# Speaker_Module.net
KiCad netlist of a schematic drawn in Altium Designer
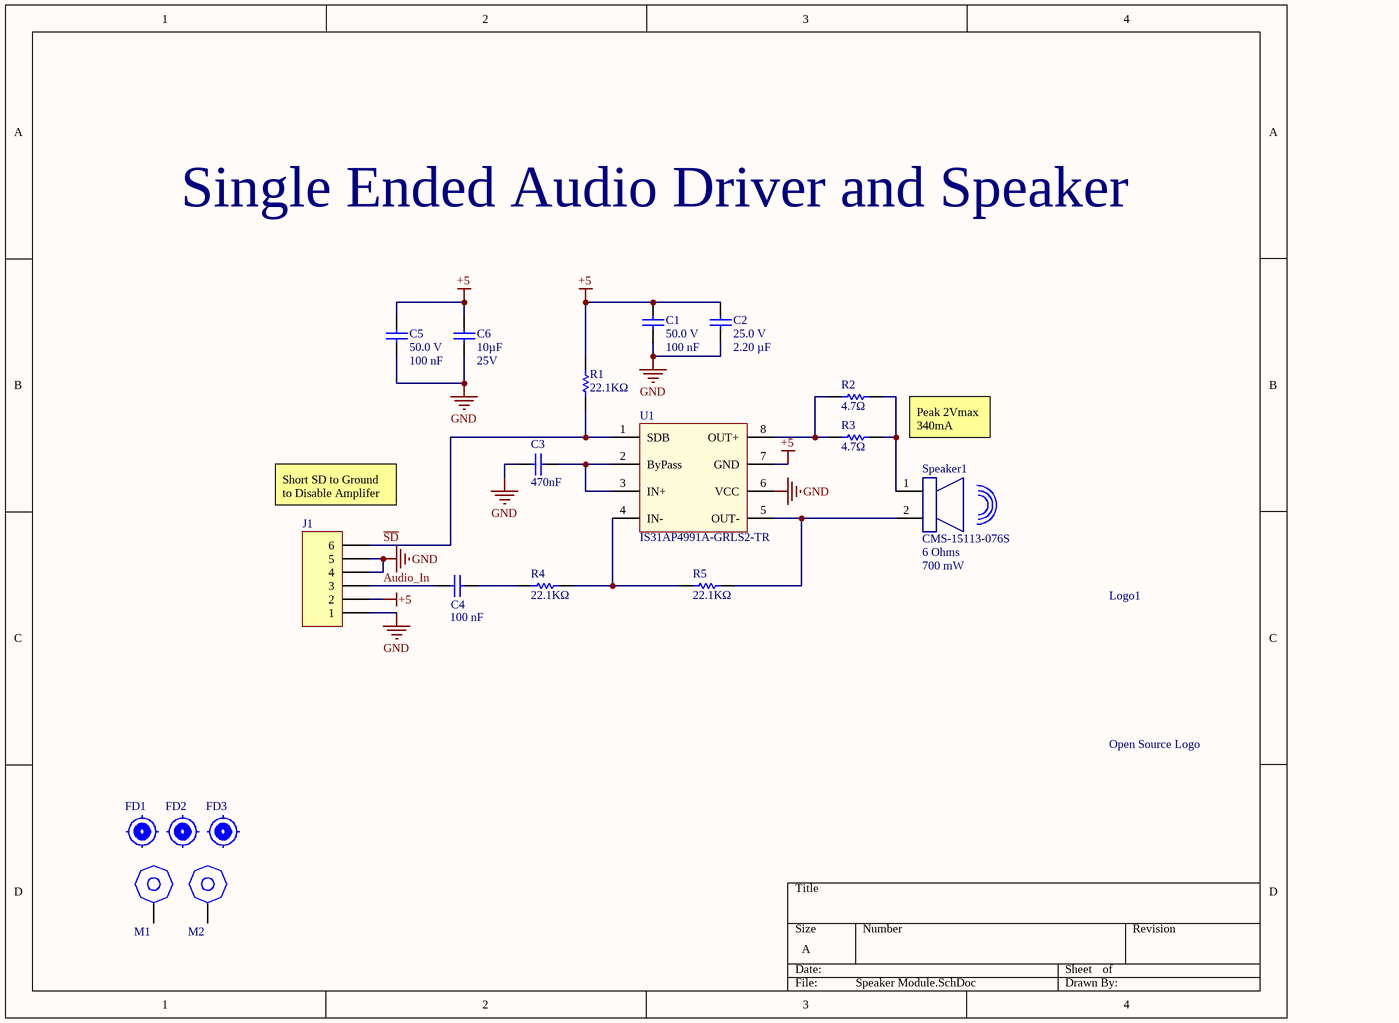
[diagram p0: Speaker Module.SchDoc]

(export (version "E")
  (design (tool "Eeschema 10.0.6"))
  (components
    (comp (ref "C1")
      (value "08055C104JAT2A")
      (footprint "Cap,0805")
      (description "Capacitor; Ceramic; Cap 0.1 uF; Tol 5%; Vol-Rtg 50 VDC; SMT; 0805; X7R; Tape & Reel")
      (fields (field (name "VOLTAGE RATING (DC)") "50.0 V") (field (name "CAPACITANCE") "100 nF"))
      (libsource (lib "Master Nov2021") (part "Cap,0805,100nf,50V,5%,08055C104JAT2A"))
    )
    (comp (ref "C2")
      (value "AVX 08053C225KAT2A")
      (footprint "CAP, 0805, HD")
      (description "0805 2.2 uF 25 V ±10 % Tolerance X7R SMT Multilayer Ceramic Capacitor")
      (fields
        (field (name "MANUFACTURER PART NUMBER") "08053C225KAT2A")
        (field (name "VOLTAGE RATING (DC)") "25.0 V")
        (field (name "CAPACITANCE") "2.20 µF")
      )
      (libsource (lib "Master Nov2021") (part "Cap,0805,2.2uF,±10%,25V,08053C225KAT2A"))
    )
    (comp (ref "C3")
      (value "CGA4J2X7R1E474K125AA")
      (footprint "Cap,0805")
      (description "0.47µF ±10% 25V Ceramic Capacitor X7R 0805 (2012 Metric)")
      (fields (field (name "MANUFACTURER") "TDK Corporation") (field (name "CAPACITANCE") "470nF"))
      (libsource (lib "Master Nov2021") (part "Cap,0805,470nf,25V,10%,CGA4J2X7R1E474K125AA"))
    )
    (comp (ref "C4")
      (value "08055C104JAT2A")
      (footprint "Cap,0805")
      (description "Capacitor; Ceramic; Cap 0.1 uF; Tol 5%; Vol-Rtg 50 VDC; SMT; 0805; X7R; Tape & Reel")
      (fields (field (name "CAPACITANCE") "100 nF"))
      (libsource (lib "Master Nov2021") (part "Cap,0805,100nf,50V,5%,08055C104JAT2A"))
    )
    (comp (ref "C5")
      (value "08055C104JAT2A")
      (footprint "Cap,0805")
      (description "Capacitor; Ceramic; Cap 0.1 uF; Tol 5%; Vol-Rtg 50 VDC; SMT; 0805; X7R; Tape & Reel")
      (fields (field (name "VOLTAGE RATING (DC)") "50.0 V") (field (name "CAPACITANCE") "100 nF"))
      (libsource (lib "Master Nov2021") (part "Cap,0805,100nf,50V,5%,08055C104JAT2A"))
    )
    (comp (ref "C6")
      (value "C3216X7R1E106K160AB")
      (footprint "Cap, 1206")
      (description "10µF ±10% 25V Ceramic Capacitor X7R 1206 (3216 Metric)")
      (fields
        (field (name "MANUFACTURER") "TDK Corporation")
        (field (name "TOLERANCE") "±10%")
        (field (name "CAPACITANCE") "10µF")
        (field (name "VOLTAGE - RATED") "25V")
      )
      (libsource (lib "Master Nov2021") (part "CAP,1206,10uF,25V,C3216X7R1E106K160AB"))
    )
    (comp (ref "FD1")
      (value "Mech,FIDU-ROUND")
      (footprint "FIDU-ROUND")
      (description "ROUND FIDUCIAL")
      (libsource (lib "Master Nov2021") (part "Mech,FIDU-ROUND"))
    )
    (comp (ref "FD2")
      (value "Mech,FIDU-ROUND")
      (footprint "FIDU-ROUND")
      (description "ROUND FIDUCIAL")
      (libsource (lib "Master Nov2021") (part "Mech,FIDU-ROUND"))
    )
    (comp (ref "FD3")
      (value "Mech,FIDU-ROUND")
      (footprint "FIDU-ROUND")
      (description "ROUND FIDUCIAL")
      (libsource (lib "Master Nov2021") (part "Mech,FIDU-ROUND"))
    )
    (comp (ref "J1")
      (value "Header, through hole,vertical, 6pin,1 Row,0.1\", M20-9991245")
      (footprint "Header, 6 pin, 0.1\" Spaceing - RA")
      (fields (field (name "MANUFACTURER PART NUMBER") "M20-9990645"))
      (libsource (lib "Master Nov2021") (part "Header, through hole,vertical, 6pin,1 Row,0.1{dblquote}, M20-9991245"))
    )
    (comp (ref "Logo1")
      (value "Open Source Logo")
      (footprint "Symbol,Open Source")
      (description "Open Source Silk Screen Logo")
      (libsource (lib "Master Mar2021") (part "Symbol,Open Source"))
    )
    (comp (ref "M1")
      (value "M3 hex Standoff")
      (footprint "Standoff,Hex,M3,8mm")
      (description "HEX STANDOFF M3,generic")
      (libsource (lib "Master Nov2021") (part "Mech,Standoff, M3, Hex"))
    )
    (comp (ref "M2")
      (value "M3 hex Standoff")
      (footprint "Standoff,Hex,M3,8mm")
      (description "HEX STANDOFF M3,generic")
      (libsource (lib "Master Nov2021") (part "Mech,Standoff, M3, Hex"))
    )
    (comp (ref "R1")
      (value "RC0805FR-0722K1L")
      (footprint "res, 0805, HD")
      (description "22.1 kOhms ±1% 0.125W, 1/8W Chip Resistor 0805 (2012 Metric) Moisture Resistant Thick Film")
      (fields (field (name "RESISTANCE") "22.1KΩ"))
      (libsource (lib "Master Nov2021") (part "Res,0805,22.1K,1%,100ppm,RC0805FR-0722K1L"))
    )
    (comp (ref "R2")
      (value "4.7Ω")
      (footprint "Res,1206")
      (libsource (lib "Master Nov2021") (part "Res,1206,Generic"))
    )
    (comp (ref "R3")
      (value "4.7Ω")
      (footprint "Res,1206")
      (libsource (lib "Master Nov2021") (part "Res,1206,Generic"))
    )
    (comp (ref "R4")
      (value "RC0805FR-0722K1L")
      (footprint "res, 0805, HD")
      (description "22.1 kOhms ±1% 0.125W, 1/8W Chip Resistor 0805 (2012 Metric) Moisture Resistant Thick Film")
      (fields (field (name "RESISTANCE") "22.1KΩ"))
      (libsource (lib "Master Nov2021") (part "Res,0805,22.1K,1%,100ppm,RC0805FR-0722K1L"))
    )
    (comp (ref "R5")
      (value "RC0805FR-0722K1L")
      (footprint "res, 0805, HD")
      (description "22.1 kOhms ±1% 0.125W, 1/8W Chip Resistor 0805 (2012 Metric) Moisture Resistant Thick Film")
      (fields (field (name "RESISTANCE") "22.1KΩ"))
      (libsource (lib "Master Nov2021") (part "Res,0805,22.1K,1%,100ppm,RC0805FR-0722K1L"))
    )
    (comp (ref "Speaker1")
      (value "CMS-15113-076S")
      (footprint "Speaker,SMD,CMS-15113-076S")
      (description "6 Ohms General Purpose Speaker 700 mW 100 Hz ~ 20 kHz Top Rectangular")
      (fields
        (field (name "MANUFACTURER") "CUI Devices")
        (field (name "IMPEDANCE") "6 Ohms")
        (field (name "POWER - RATED") "700 mW")
      )
      (libsource (lib "Master Nov2021") (part "Speaker,SMD,6Ω,700mW,Magnetic,100 Hz ~ 20 kHz,CMS-15113-076S"))
    )
    (comp (ref "U1")
      (value "IS31AP4991A-GRLS2-TR")
      (footprint "SOIC-8")
      (description "IC AMP CLASS AB MONO 1.15W 8SOIC")
      (fields (field (name "MFR") "Lumissil Microsystems"))
      (libsource (lib "Master Nov2021") (part "IC,PowerAmp,ClassAB,1.15W x 1 @ 8Ohm,2.7V ~ 5.5V,IS31AP4991"))
    )
  )
  (nets
    (net (code "1") (name "+5") (class "Default")
      (node (ref "C1") (pin "1") (pinfunction "1_1") (pintype "passive"))
      (node (ref "C2") (pin "2") (pinfunction "2_2") (pintype "passive"))
      (node (ref "C5") (pin "1") (pinfunction "1_1") (pintype "passive"))
      (node (ref "C6") (pin "2") (pinfunction "2_2") (pintype "passive"))
      (node (ref "J1") (pin "2") (pinfunction "2_2") (pintype "passive"))
      (node (ref "R1") (pin "1") (pinfunction "1_1") (pintype "passive"))
      (node (ref "U1") (pin "7") (pinfunction "GND_7") (pintype "passive"))
    )
    (net (code "2") (name "/Audio_In") (class "Default")
      (node (ref "C4") (pin "1") (pinfunction "1_1") (pintype "passive"))
      (node (ref "J1") (pin "3") (pinfunction "3_3") (pintype "passive"))
    )
    (net (code "3") (name "/~{SD}") (class "Default")
      (node (ref "J1") (pin "6") (pinfunction "6_6") (pintype "passive"))
      (node (ref "R1") (pin "2") (pinfunction "2_2") (pintype "passive"))
      (node (ref "U1") (pin "1") (pinfunction "SDB_1") (pintype "passive"))
    )
    (net (code "4") (name "GND") (class "Default")
      (node (ref "C1") (pin "2") (pinfunction "2_2") (pintype "passive"))
      (node (ref "C2") (pin "1") (pinfunction "1_1") (pintype "passive"))
      (node (ref "C3") (pin "2") (pinfunction "2_2") (pintype "passive"))
      (node (ref "C5") (pin "2") (pinfunction "2_2") (pintype "passive"))
      (node (ref "C6") (pin "1") (pinfunction "1_1") (pintype "passive"))
      (node (ref "J1") (pin "1") (pinfunction "1_1") (pintype "passive"))
      (node (ref "J1") (pin "4") (pinfunction "4_4") (pintype "passive"))
      (node (ref "J1") (pin "5") (pinfunction "5_5") (pintype "passive"))
      (node (ref "U1") (pin "6") (pinfunction "VCC_6") (pintype "passive"))
    )
    (net (code "5") (name "Net-(C4-Pad2)") (class "Default")
      (node (ref "C4") (pin "2") (pinfunction "2_2") (pintype "passive"))
      (node (ref "R4") (pin "2") (pinfunction "2_2") (pintype "passive"))
    )
    (net (code "6") (name "Net-(R2-Pad1)") (class "Default")
      (node (ref "R2") (pin "1") (pinfunction "1_1") (pintype "passive"))
      (node (ref "R3") (pin "1") (pinfunction "1_1") (pintype "passive"))
      (node (ref "Speaker1") (pin "1") (pinfunction "1_1") (pintype "passive"))
    )
    (net (code "7") (name "Net-(U1-ByPass)") (class "Default")
      (node (ref "C3") (pin "1") (pinfunction "1_1") (pintype "passive"))
      (node (ref "U1") (pin "2") (pinfunction "ByPass_2") (pintype "passive"))
      (node (ref "U1") (pin "3") (pinfunction "IN+_3") (pintype "passive"))
    )
    (net (code "8") (name "Net-(U1-IN-)") (class "Default")
      (node (ref "R4") (pin "1") (pinfunction "1_1") (pintype "passive"))
      (node (ref "R5") (pin "2") (pinfunction "2_2") (pintype "passive"))
      (node (ref "U1") (pin "4") (pinfunction "IN-_4") (pintype "passive"))
    )
    (net (code "9") (name "Net-(U1-OUT+)") (class "Default")
      (node (ref "R2") (pin "2") (pinfunction "2_2") (pintype "passive"))
      (node (ref "R3") (pin "2") (pinfunction "2_2") (pintype "passive"))
      (node (ref "U1") (pin "8") (pinfunction "OUT+_8") (pintype "passive"))
    )
    (net (code "10") (name "Net-(U1-OUT-)") (class "Default")
      (node (ref "R5") (pin "1") (pinfunction "1_1") (pintype "passive"))
      (node (ref "Speaker1") (pin "2") (pinfunction "2_2") (pintype "passive"))
      (node (ref "U1") (pin "5") (pinfunction "OUT-_5") (pintype "passive"))
    )
    (net (code "11") (name "unconnected-(M1-Pad0)") (class "Default")
      (node (ref "M1") (pin "0") (pinfunction "0_0") (pintype "passive"))
    )
    (net (code "12") (name "unconnected-(M2-Pad0)") (class "Default")
      (node (ref "M2") (pin "0") (pinfunction "0_0") (pintype "passive"))
    )
  )
)
